# Gate_Drivers.net
KiCad netlist of a schematic drawn in Altium Designer
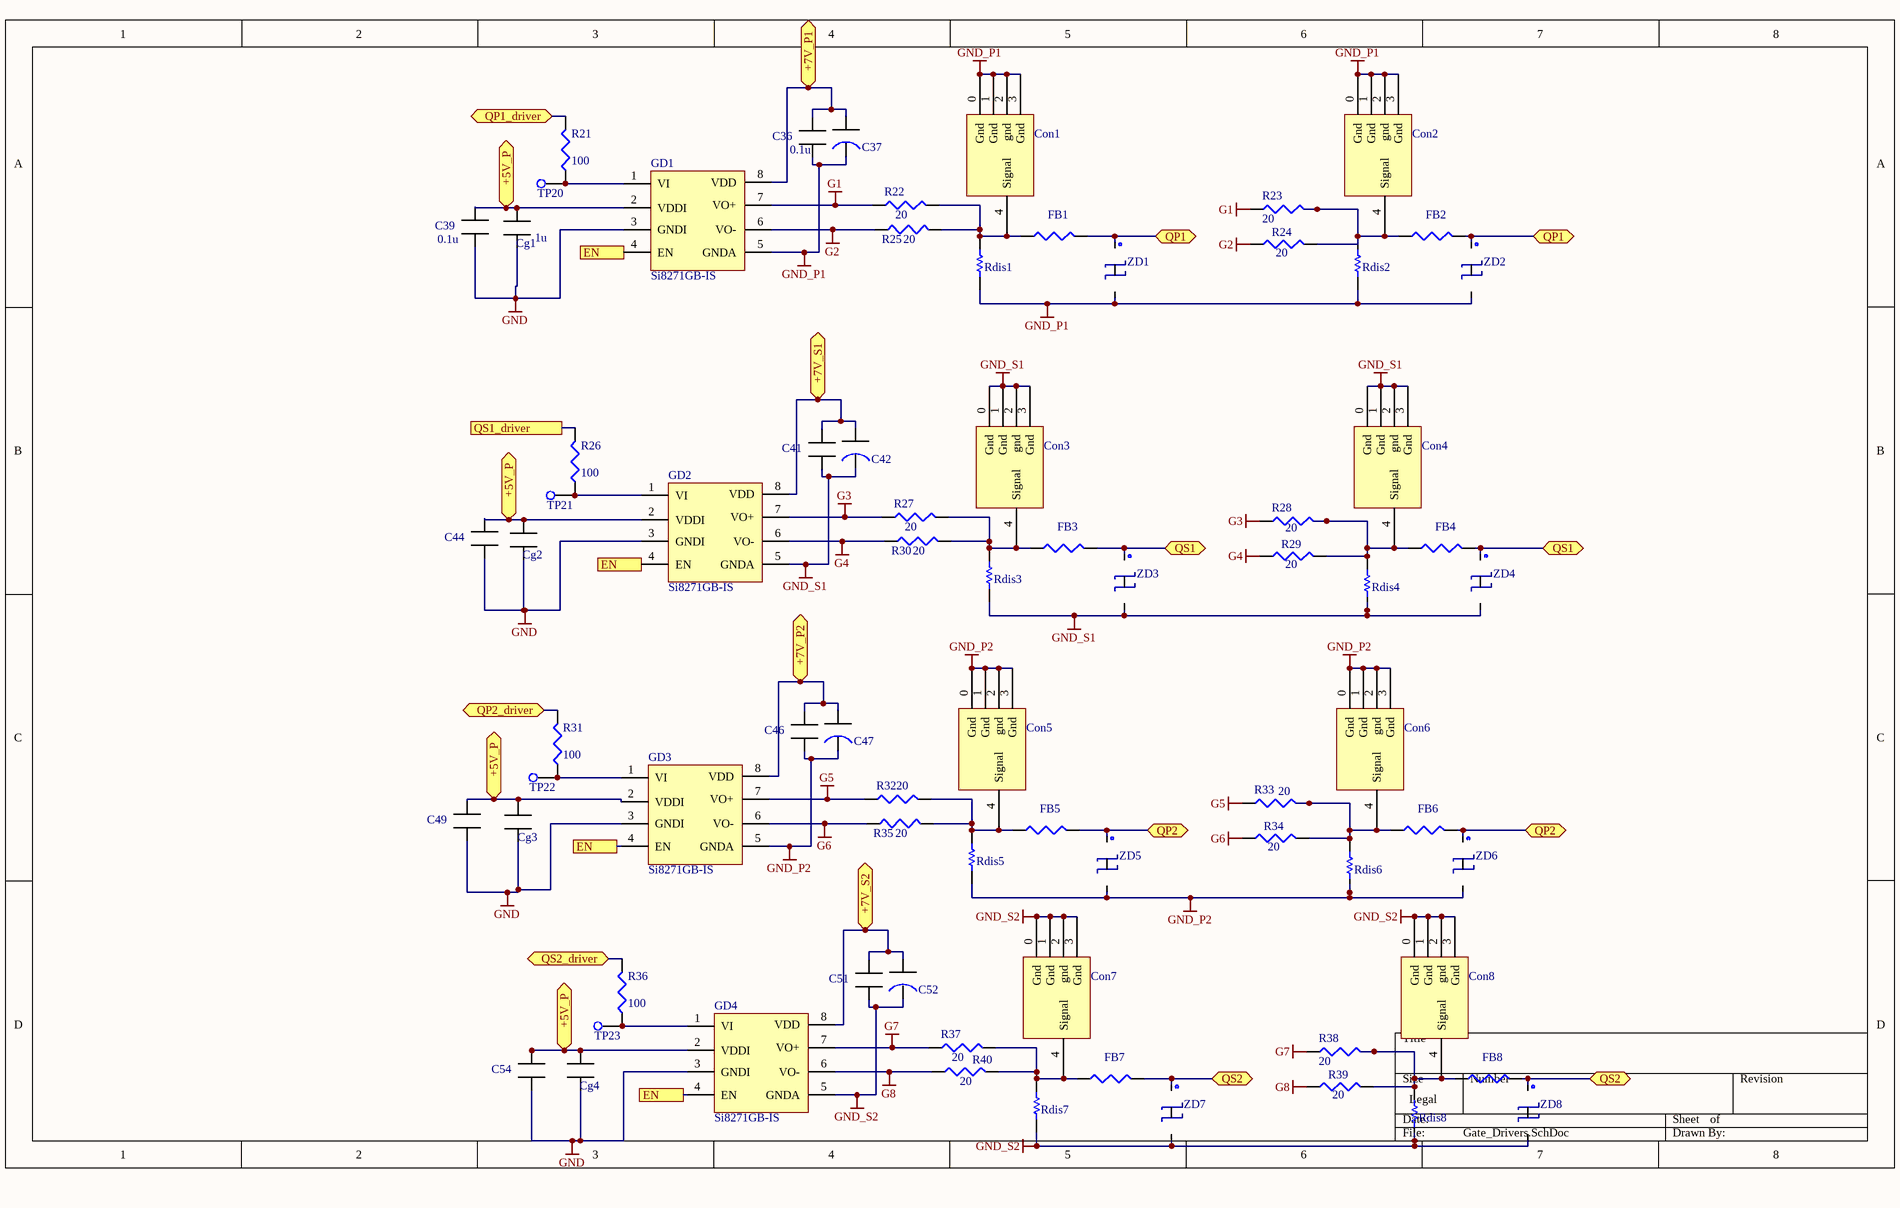
[diagram p0: Gate_Drivers.SchDoc]

(export (version "E")
  (design (tool "Eeschema 10.0.6"))
  (components
    (comp (ref "C36")
      (value "100nF")
      (footprint "Cap_SMD")
      (fields (field (name "ALTIUM_UNNAMED_1") "0.1u"))
      (libsource (lib "Schlib1") (part "Cap_SMD"))
    )
    (comp (ref "C37")
      (value "22uF")
      (footprint "Cap_tantalum")
      (libsource (lib "Schlib1") (part "Cap_tantalum"))
    )
    (comp (ref "C39")
      (value "100nF")
      (footprint "Cap_SMD")
      (fields (field (name "ALTIUM_UNNAMED_1") "0.1u"))
      (libsource (lib "Schlib1") (part "Cap_SMD"))
    )
    (comp (ref "C41") (value "100nF") (footprint "Cap_SMD") (libsource (lib "Schlib1") (part "Cap_SMD")))
    (comp (ref "C42")
      (value "22uF")
      (footprint "Cap_tantalum")
      (libsource (lib "Schlib1") (part "Cap_tantalum"))
    )
    (comp (ref "C44") (value "100nF") (footprint "Cap_SMD") (libsource (lib "Schlib1") (part "Cap_SMD")))
    (comp (ref "C46") (value "100nF") (footprint "Cap_SMD") (libsource (lib "Schlib1") (part "Cap_SMD")))
    (comp (ref "C47")
      (value "22uF")
      (footprint "Cap_tantalum")
      (libsource (lib "Schlib1") (part "Cap_tantalum"))
    )
    (comp (ref "C49") (value "100nF") (footprint "Cap_SMD") (libsource (lib "Schlib1") (part "Cap_SMD")))
    (comp (ref "C51") (value "100nF") (footprint "Cap_SMD") (libsource (lib "Schlib1") (part "Cap_SMD")))
    (comp (ref "C52")
      (value "22uF")
      (footprint "Cap_tantalum")
      (libsource (lib "Schlib1") (part "Cap_tantalum"))
    )
    (comp (ref "C54") (value "100nF") (footprint "Cap_SMD") (libsource (lib "Schlib1") (part "Cap_SMD")))
    (comp (ref "Cg1")
      (value "100nF")
      (footprint "Cap_SMD")
      (fields (field (name "ALTIUM_UNNAMED_1") "1u"))
      (libsource (lib "Schlib1") (part "Cap_SMD"))
    )
    (comp (ref "Cg2") (value "100nF") (footprint "Cap_SMD") (libsource (lib "Schlib1") (part "Cap_SMD")))
    (comp (ref "Cg3") (value "100nF") (footprint "Cap_SMD") (libsource (lib "Schlib1") (part "Cap_SMD")))
    (comp (ref "Cg4") (value "100nF") (footprint "Cap_SMD") (libsource (lib "Schlib1") (part "Cap_SMD")))
    (comp (ref "Con1")
      (value "Component_1")
      (footprint "PCBComponent_1")
      (libsource (lib "pcb_connector") (part "Component_1"))
    )
    (comp (ref "Con2")
      (value "Component_1")
      (footprint "PCBComponent_1")
      (libsource (lib "pcb_connector") (part "Component_1"))
    )
    (comp (ref "Con3")
      (value "Component_1")
      (footprint "PCBComponent_1")
      (libsource (lib "pcb_connector") (part "Component_1"))
    )
    (comp (ref "Con4")
      (value "Component_1")
      (footprint "PCBComponent_1")
      (libsource (lib "pcb_connector") (part "Component_1"))
    )
    (comp (ref "Con5")
      (value "Component_1")
      (footprint "PCBComponent_1")
      (libsource (lib "pcb_connector") (part "Component_1"))
    )
    (comp (ref "Con6")
      (value "Component_1")
      (footprint "PCBComponent_1")
      (libsource (lib "pcb_connector") (part "Component_1"))
    )
    (comp (ref "Con7")
      (value "Component_1")
      (footprint "PCBComponent_1")
      (libsource (lib "pcb_connector") (part "Component_1"))
    )
    (comp (ref "Con8")
      (value "Component_1")
      (footprint "PCBComponent_1")
      (libsource (lib "pcb_connector") (part "Component_1"))
    )
    (comp (ref "FB1")
      (value "Res3")
      (footprint "J1-0603")
      (description "Resistor")
      (fields (field (name "PUBLISHER") "Altium Limited"))
      (libsource (lib "Miscellaneous Devices") (part "Res3"))
    )
    (comp (ref "FB2")
      (value "Res3")
      (footprint "J1-0603")
      (description "Resistor")
      (fields (field (name "PUBLISHER") "Altium Limited"))
      (libsource (lib "Miscellaneous Devices") (part "Res3"))
    )
    (comp (ref "FB3")
      (value "Res3")
      (footprint "J1-0603")
      (description "Resistor")
      (fields (field (name "PUBLISHER") "Altium Limited"))
      (libsource (lib "Miscellaneous Devices") (part "Res3"))
    )
    (comp (ref "FB4")
      (value "Res3")
      (footprint "J1-0603")
      (description "Resistor")
      (fields (field (name "PUBLISHER") "Altium Limited"))
      (libsource (lib "Miscellaneous Devices") (part "Res3"))
    )
    (comp (ref "FB5")
      (value "Res3")
      (footprint "J1-0603")
      (description "Resistor")
      (fields (field (name "PUBLISHER") "Altium Limited"))
      (libsource (lib "Miscellaneous Devices") (part "Res3"))
    )
    (comp (ref "FB6")
      (value "Res3")
      (footprint "J1-0603")
      (description "Resistor")
      (fields (field (name "PUBLISHER") "Altium Limited"))
      (libsource (lib "Miscellaneous Devices") (part "Res3"))
    )
    (comp (ref "FB7")
      (value "Res3")
      (footprint "J1-0603")
      (description "Resistor")
      (fields (field (name "PUBLISHER") "Altium Limited"))
      (libsource (lib "Miscellaneous Devices") (part "Res3"))
    )
    (comp (ref "FB8")
      (value "Res3")
      (footprint "J1-0603")
      (description "Resistor")
      (fields (field (name "PUBLISHER") "Altium Limited"))
      (libsource (lib "Miscellaneous Devices") (part "Res3"))
    )
    (comp (ref "GD1")
      (value "Si8271GB-IS")
      (footprint "Si8271")
      (libsource (lib "Gan_cuk converter") (part "Si8271GB-IS"))
    )
    (comp (ref "GD2")
      (value "Si8271GB-IS")
      (footprint "Si8271")
      (libsource (lib "Gan_cuk converter") (part "Si8271GB-IS"))
    )
    (comp (ref "GD3")
      (value "Si8271GB-IS")
      (footprint "Si8271")
      (libsource (lib "Gan_cuk converter") (part "Si8271GB-IS"))
    )
    (comp (ref "GD4")
      (value "Si8271GB-IS")
      (footprint "Si8271")
      (libsource (lib "Gan_cuk converter") (part "Si8271GB-IS"))
    )
    (comp (ref "R21")
      (value "100")
      (footprint "J1-0603")
      (description "Resistor")
      (fields (field (name "Comment") "Res3") (field (name "PUBLISHER") "Altium Limited"))
      (libsource (lib "Miscellaneous Devices") (part "Res3"))
    )
    (comp (ref "R22")
      (value "20")
      (footprint "J1-0603")
      (description "Resistor")
      (fields (field (name "Comment") "Res3") (field (name "PUBLISHER") "Altium Limited"))
      (libsource (lib "Miscellaneous Devices") (part "Res3"))
    )
    (comp (ref "R23")
      (value "20")
      (footprint "J1-0603")
      (description "Resistor")
      (fields (field (name "Comment") "Res3") (field (name "PUBLISHER") "Altium Limited"))
      (libsource (lib "Miscellaneous Devices") (part "Res3"))
    )
    (comp (ref "R24")
      (value "20")
      (footprint "J1-0603")
      (description "Resistor")
      (fields (field (name "PUBLISHER") "Altium Limited"))
      (libsource (lib "Miscellaneous Devices") (part "Res3"))
    )
    (comp (ref "R25")
      (value "20")
      (footprint "J1-0603")
      (description "Resistor")
      (fields (field (name "Comment") "Res3") (field (name "PUBLISHER") "Altium Limited"))
      (libsource (lib "Miscellaneous Devices") (part "Res3"))
    )
    (comp (ref "R26")
      (value "100")
      (footprint "J1-0603")
      (description "Resistor")
      (fields (field (name "Comment") "Res3") (field (name "PUBLISHER") "Altium Limited"))
      (libsource (lib "Miscellaneous Devices") (part "Res3"))
    )
    (comp (ref "R27")
      (value "20")
      (footprint "J1-0603")
      (description "Resistor")
      (fields (field (name "Comment") "Res3") (field (name "PUBLISHER") "Altium Limited"))
      (libsource (lib "Miscellaneous Devices") (part "Res3"))
    )
    (comp (ref "R28")
      (value "20")
      (footprint "J1-0603")
      (description "Resistor")
      (fields (field (name "Comment") "Res3") (field (name "PUBLISHER") "Altium Limited"))
      (libsource (lib "Miscellaneous Devices") (part "Res3"))
    )
    (comp (ref "R29")
      (value "20")
      (footprint "J1-0603")
      (description "Resistor")
      (fields (field (name "PUBLISHER") "Altium Limited"))
      (libsource (lib "Miscellaneous Devices") (part "Res3"))
    )
    (comp (ref "R30")
      (value "20")
      (footprint "J1-0603")
      (description "Resistor")
      (fields (field (name "Comment") "Res3") (field (name "PUBLISHER") "Altium Limited"))
      (libsource (lib "Miscellaneous Devices") (part "Res3"))
    )
    (comp (ref "R31")
      (value "100")
      (footprint "J1-0603")
      (description "Resistor")
      (fields (field (name "Comment") "Res3") (field (name "PUBLISHER") "Altium Limited"))
      (libsource (lib "Miscellaneous Devices") (part "Res3"))
    )
    (comp (ref "R32")
      (value "20")
      (footprint "J1-0603")
      (description "Resistor")
      (fields (field (name "Comment") "Res3") (field (name "PUBLISHER") "Altium Limited"))
      (libsource (lib "Miscellaneous Devices") (part "Res3"))
    )
    (comp (ref "R33")
      (value "20")
      (footprint "J1-0603")
      (description "Resistor")
      (fields (field (name "Comment") "Res3") (field (name "PUBLISHER") "Altium Limited"))
      (libsource (lib "Miscellaneous Devices") (part "Res3"))
    )
    (comp (ref "R34")
      (value "20")
      (footprint "J1-0603")
      (description "Resistor")
      (fields (field (name "PUBLISHER") "Altium Limited"))
      (libsource (lib "Miscellaneous Devices") (part "Res3"))
    )
    (comp (ref "R35")
      (value "20")
      (footprint "J1-0603")
      (description "Resistor")
      (fields (field (name "Comment") "Res3") (field (name "PUBLISHER") "Altium Limited"))
      (libsource (lib "Miscellaneous Devices") (part "Res3"))
    )
    (comp (ref "R36")
      (value "100")
      (footprint "J1-0603")
      (description "Resistor")
      (fields (field (name "Comment") "Res3") (field (name "PUBLISHER") "Altium Limited"))
      (libsource (lib "Miscellaneous Devices") (part "Res3"))
    )
    (comp (ref "R37")
      (value "20")
      (footprint "J1-0603")
      (description "Resistor")
      (fields (field (name "Comment") "Res3") (field (name "PUBLISHER") "Altium Limited"))
      (libsource (lib "Miscellaneous Devices") (part "Res3"))
    )
    (comp (ref "R38")
      (value "20")
      (footprint "J1-0603")
      (description "Resistor")
      (fields (field (name "Comment") "Res3") (field (name "PUBLISHER") "Altium Limited"))
      (libsource (lib "Miscellaneous Devices") (part "Res3"))
    )
    (comp (ref "R39")
      (value "20")
      (footprint "J1-0603")
      (description "Resistor")
      (fields (field (name "PUBLISHER") "Altium Limited"))
      (libsource (lib "Miscellaneous Devices") (part "Res3"))
    )
    (comp (ref "R40")
      (value "20")
      (footprint "J1-0603")
      (description "Resistor")
      (fields (field (name "Comment") "Res3") (field (name "PUBLISHER") "Altium Limited"))
      (libsource (lib "Miscellaneous Devices") (part "Res3"))
    )
    (comp (ref "Rdis1")
      (value "res_smd")
      (footprint "J1-0603")
      (description "smd_res")
      (libsource (lib "Schlib1") (part "res_smd"))
    )
    (comp (ref "Rdis2")
      (value "res_smd")
      (footprint "J1-0603")
      (description "smd_res")
      (libsource (lib "Schlib1") (part "res_smd"))
    )
    (comp (ref "Rdis3")
      (value "res_smd")
      (footprint "J1-0603")
      (description "smd_res")
      (libsource (lib "Schlib1") (part "res_smd"))
    )
    (comp (ref "Rdis4")
      (value "res_smd")
      (footprint "J1-0603")
      (description "smd_res")
      (libsource (lib "Schlib1") (part "res_smd"))
    )
    (comp (ref "Rdis5")
      (value "res_smd")
      (footprint "J1-0603")
      (description "smd_res")
      (libsource (lib "Schlib1") (part "res_smd"))
    )
    (comp (ref "Rdis6")
      (value "res_smd")
      (footprint "J1-0603")
      (description "smd_res")
      (libsource (lib "Schlib1") (part "res_smd"))
    )
    (comp (ref "Rdis7")
      (value "res_smd")
      (footprint "J1-0603")
      (description "smd_res")
      (libsource (lib "Schlib1") (part "res_smd"))
    )
    (comp (ref "Rdis8")
      (value "res_smd")
      (footprint "J1-0603")
      (description "smd_res")
      (libsource (lib "Schlib1") (part "res_smd"))
    )
    (comp (ref "TP20")
      (value "Test Point")
      (footprint "Test Point")
      (libsource (lib "Gan_cuk converter") (part "Test Point"))
    )
    (comp (ref "TP21")
      (value "Test Point")
      (footprint "Test Point")
      (libsource (lib "Gan_cuk converter") (part "Test Point"))
    )
    (comp (ref "TP22")
      (value "Test Point")
      (footprint "Test Point")
      (libsource (lib "Gan_cuk converter") (part "Test Point"))
    )
    (comp (ref "TP23")
      (value "Test Point")
      (footprint "Test Point")
      (libsource (lib "Gan_cuk converter") (part "Test Point"))
    )
    (comp (ref "ZD1")
      (value "8.2 v")
      (footprint "Zener Diode")
      (description "DZ23C8V2-7-F")
      (libsource (lib "Gan_cuk converter") (part "Zener_diode"))
    )
    (comp (ref "ZD2")
      (value "8.2 v")
      (footprint "Zener Diode")
      (description "DZ23C8V2-7-F")
      (libsource (lib "Gan_cuk converter") (part "Zener_diode"))
    )
    (comp (ref "ZD3")
      (value "8.2 v")
      (footprint "Zener Diode")
      (description "DZ23C8V2-7-F")
      (libsource (lib "Gan_cuk converter") (part "Zener_diode"))
    )
    (comp (ref "ZD4")
      (value "8.2 v")
      (footprint "Zener Diode")
      (description "DZ23C8V2-7-F")
      (libsource (lib "Gan_cuk converter") (part "Zener_diode"))
    )
    (comp (ref "ZD5")
      (value "8.2 v")
      (footprint "Zener Diode")
      (description "DZ23C8V2-7-F")
      (libsource (lib "Gan_cuk converter") (part "Zener_diode"))
    )
    (comp (ref "ZD6")
      (value "8.2 v")
      (footprint "Zener Diode")
      (description "DZ23C8V2-7-F")
      (libsource (lib "Gan_cuk converter") (part "Zener_diode"))
    )
    (comp (ref "ZD7")
      (value "8.2 v")
      (footprint "Zener Diode")
      (description "DZ23C8V2-7-F")
      (libsource (lib "Gan_cuk converter") (part "Zener_diode"))
    )
    (comp (ref "ZD8")
      (value "8.2 v")
      (footprint "Zener Diode")
      (description "DZ23C8V2-7-F")
      (libsource (lib "Gan_cuk converter") (part "Zener_diode"))
    )
  )
  (nets
    (net (code "1") (name "/+5V_P") (class "Default")
      (node (ref "C39") (pin "1") (pintype "passive"))
      (node (ref "C44") (pin "1") (pintype "passive"))
      (node (ref "C49") (pin "1") (pintype "passive"))
      (node (ref "C54") (pin "1") (pintype "passive"))
      (node (ref "Cg1") (pin "1") (pintype "passive"))
      (node (ref "Cg2") (pin "1") (pintype "passive"))
      (node (ref "Cg3") (pin "1") (pintype "passive"))
      (node (ref "Cg4") (pin "1") (pintype "passive"))
      (node (ref "GD1") (pin "2") (pinfunction "VDDI_2") (pintype "passive"))
      (node (ref "GD2") (pin "2") (pinfunction "VDDI_2") (pintype "passive"))
      (node (ref "GD3") (pin "2") (pinfunction "VDDI_2") (pintype "passive"))
      (node (ref "GD4") (pin "2") (pinfunction "VDDI_2") (pintype "passive"))
    )
    (net (code "2") (name "/+7V_P1") (class "Default")
      (node (ref "C36") (pin "1") (pintype "passive"))
      (node (ref "C37") (pin "1") (pintype "passive"))
      (node (ref "GD1") (pin "8") (pinfunction "VDD_8") (pintype "passive"))
    )
    (net (code "3") (name "/+7V_P2") (class "Default")
      (node (ref "C46") (pin "1") (pintype "passive"))
      (node (ref "C47") (pin "1") (pintype "passive"))
      (node (ref "GD3") (pin "8") (pinfunction "VDD_8") (pintype "passive"))
    )
    (net (code "4") (name "/+7V_S1") (class "Default")
      (node (ref "C41") (pin "1") (pintype "passive"))
      (node (ref "C42") (pin "1") (pintype "passive"))
      (node (ref "GD2") (pin "8") (pinfunction "VDD_8") (pintype "passive"))
    )
    (net (code "5") (name "/+7V_S2") (class "Default")
      (node (ref "C51") (pin "1") (pintype "passive"))
      (node (ref "C52") (pin "1") (pintype "passive"))
      (node (ref "GD4") (pin "8") (pinfunction "VDD_8") (pintype "passive"))
    )
    (net (code "6") (name "/EN") (class "Default")
      (node (ref "GD1") (pin "4") (pinfunction "EN_4") (pintype "passive"))
      (node (ref "GD2") (pin "4") (pinfunction "EN_4") (pintype "passive"))
      (node (ref "GD3") (pin "4") (pinfunction "EN_4") (pintype "passive"))
      (node (ref "GD4") (pin "4") (pinfunction "EN_4") (pintype "passive"))
    )
    (net (code "7") (name "/QP1") (class "Default")
      (node (ref "FB1") (pin "2") (pinfunction "2_2") (pintype "passive"))
      (node (ref "FB2") (pin "2") (pinfunction "2_2") (pintype "passive"))
      (node (ref "ZD1") (pin "1") (pinfunction "1_1") (pintype "passive"))
      (node (ref "ZD2") (pin "1") (pinfunction "1_1") (pintype "passive"))
    )
    (net (code "8") (name "/QP1_driver") (class "Default")
      (node (ref "R21") (pin "2") (pinfunction "2_2") (pintype "passive"))
    )
    (net (code "9") (name "/QP2") (class "Default")
      (node (ref "FB5") (pin "2") (pinfunction "2_2") (pintype "passive"))
      (node (ref "FB6") (pin "2") (pinfunction "2_2") (pintype "passive"))
      (node (ref "ZD5") (pin "1") (pinfunction "1_1") (pintype "passive"))
      (node (ref "ZD6") (pin "1") (pinfunction "1_1") (pintype "passive"))
    )
    (net (code "10") (name "/QP2_driver") (class "Default")
      (node (ref "R31") (pin "2") (pinfunction "2_2") (pintype "passive"))
    )
    (net (code "11") (name "/QS1") (class "Default")
      (node (ref "FB3") (pin "2") (pinfunction "2_2") (pintype "passive"))
      (node (ref "FB4") (pin "2") (pinfunction "2_2") (pintype "passive"))
      (node (ref "ZD3") (pin "1") (pinfunction "1_1") (pintype "passive"))
      (node (ref "ZD4") (pin "1") (pinfunction "1_1") (pintype "passive"))
    )
    (net (code "12") (name "/QS1_driver") (class "Default")
      (node (ref "R26") (pin "2") (pinfunction "2_2") (pintype "passive"))
    )
    (net (code "13") (name "/QS2") (class "Default")
      (node (ref "FB7") (pin "2") (pinfunction "2_2") (pintype "passive"))
      (node (ref "FB8") (pin "2") (pinfunction "2_2") (pintype "passive"))
      (node (ref "ZD7") (pin "1") (pinfunction "1_1") (pintype "passive"))
      (node (ref "ZD8") (pin "1") (pinfunction "1_1") (pintype "passive"))
    )
    (net (code "14") (name "/QS2_driver") (class "Default")
      (node (ref "R36") (pin "2") (pinfunction "2_2") (pintype "passive"))
    )
    (net (code "15") (name "G1") (class "Default")
      (node (ref "GD1") (pin "7") (pinfunction "VO+_7") (pintype "passive"))
      (node (ref "R22") (pin "1") (pinfunction "1_1") (pintype "passive"))
      (node (ref "R23") (pin "1") (pinfunction "1_1") (pintype "passive"))
    )
    (net (code "16") (name "G2") (class "Default")
      (node (ref "GD1") (pin "6") (pinfunction "VO-_6") (pintype "passive"))
      (node (ref "R24") (pin "1") (pinfunction "1_1") (pintype "passive"))
      (node (ref "R25") (pin "1") (pinfunction "1_1") (pintype "passive"))
    )
    (net (code "17") (name "G3") (class "Default")
      (node (ref "GD2") (pin "7") (pinfunction "VO+_7") (pintype "passive"))
      (node (ref "R27") (pin "1") (pinfunction "1_1") (pintype "passive"))
      (node (ref "R28") (pin "1") (pinfunction "1_1") (pintype "passive"))
    )
    (net (code "18") (name "G4") (class "Default")
      (node (ref "GD2") (pin "6") (pinfunction "VO-_6") (pintype "passive"))
      (node (ref "R29") (pin "1") (pinfunction "1_1") (pintype "passive"))
      (node (ref "R30") (pin "1") (pinfunction "1_1") (pintype "passive"))
    )
    (net (code "19") (name "G5") (class "Default")
      (node (ref "GD3") (pin "7") (pinfunction "VO+_7") (pintype "passive"))
      (node (ref "R32") (pin "1") (pinfunction "1_1") (pintype "passive"))
      (node (ref "R33") (pin "1") (pinfunction "1_1") (pintype "passive"))
    )
    (net (code "20") (name "G6") (class "Default")
      (node (ref "GD3") (pin "6") (pinfunction "VO-_6") (pintype "passive"))
      (node (ref "R34") (pin "1") (pinfunction "1_1") (pintype "passive"))
      (node (ref "R35") (pin "1") (pinfunction "1_1") (pintype "passive"))
    )
    (net (code "21") (name "G7") (class "Default")
      (node (ref "GD4") (pin "7") (pinfunction "VO+_7") (pintype "passive"))
      (node (ref "R37") (pin "1") (pinfunction "1_1") (pintype "passive"))
      (node (ref "R38") (pin "1") (pinfunction "1_1") (pintype "passive"))
    )
    (net (code "22") (name "G8") (class "Default")
      (node (ref "GD4") (pin "6") (pinfunction "VO-_6") (pintype "passive"))
      (node (ref "R39") (pin "1") (pinfunction "1_1") (pintype "passive"))
      (node (ref "R40") (pin "1") (pinfunction "1_1") (pintype "passive"))
    )
    (net (code "23") (name "GND") (class "Default")
      (node (ref "C39") (pin "2") (pintype "passive"))
      (node (ref "C44") (pin "2") (pintype "passive"))
      (node (ref "C49") (pin "2") (pintype "passive"))
      (node (ref "C54") (pin "2") (pintype "passive"))
      (node (ref "Cg1") (pin "2") (pintype "passive"))
      (node (ref "Cg2") (pin "2") (pintype "passive"))
      (node (ref "Cg3") (pin "2") (pintype "passive"))
      (node (ref "Cg4") (pin "2") (pintype "passive"))
      (node (ref "GD1") (pin "3") (pinfunction "GNDI_3") (pintype "passive"))
      (node (ref "GD2") (pin "3") (pinfunction "GNDI_3") (pintype "passive"))
      (node (ref "GD3") (pin "3") (pinfunction "GNDI_3") (pintype "passive"))
      (node (ref "GD4") (pin "3") (pinfunction "GNDI_3") (pintype "passive"))
    )
    (net (code "24") (name "GND_P1") (class "Default")
      (node (ref "C36") (pin "2") (pintype "passive"))
      (node (ref "C37") (pin "2") (pintype "passive"))
      (node (ref "Con1") (pin "0") (pinfunction "Gnd_0") (pintype "passive"))
      (node (ref "Con1") (pin "1") (pinfunction "Gnd_1") (pintype "passive"))
      (node (ref "Con1") (pin "2") (pinfunction "gnd_2") (pintype "passive"))
      (node (ref "Con1") (pin "3") (pinfunction "Gnd_3") (pintype "passive"))
      (node (ref "Con2") (pin "0") (pinfunction "Gnd_0") (pintype "passive"))
      (node (ref "Con2") (pin "1") (pinfunction "Gnd_1") (pintype "passive"))
      (node (ref "Con2") (pin "2") (pinfunction "gnd_2") (pintype "passive"))
      (node (ref "Con2") (pin "3") (pinfunction "Gnd_3") (pintype "passive"))
      (node (ref "GD1") (pin "5") (pinfunction "GNDA_5") (pintype "passive"))
      (node (ref "Rdis1") (pin "2") (pintype "passive"))
      (node (ref "Rdis2") (pin "2") (pintype "passive"))
      (node (ref "ZD1") (pin "2") (pinfunction "2_2") (pintype "passive"))
      (node (ref "ZD2") (pin "2") (pinfunction "2_2") (pintype "passive"))
    )
    (net (code "25") (name "GND_P2") (class "Default")
      (node (ref "C46") (pin "2") (pintype "passive"))
      (node (ref "C47") (pin "2") (pintype "passive"))
      (node (ref "Con5") (pin "0") (pinfunction "Gnd_0") (pintype "passive"))
      (node (ref "Con5") (pin "1") (pinfunction "Gnd_1") (pintype "passive"))
      (node (ref "Con5") (pin "2") (pinfunction "gnd_2") (pintype "passive"))
      (node (ref "Con5") (pin "3") (pinfunction "Gnd_3") (pintype "passive"))
      (node (ref "Con6") (pin "0") (pinfunction "Gnd_0") (pintype "passive"))
      (node (ref "Con6") (pin "1") (pinfunction "Gnd_1") (pintype "passive"))
      (node (ref "Con6") (pin "2") (pinfunction "gnd_2") (pintype "passive"))
      (node (ref "Con6") (pin "3") (pinfunction "Gnd_3") (pintype "passive"))
      (node (ref "GD3") (pin "5") (pinfunction "GNDA_5") (pintype "passive"))
      (node (ref "Rdis5") (pin "2") (pintype "passive"))
      (node (ref "Rdis6") (pin "2") (pintype "passive"))
      (node (ref "ZD5") (pin "2") (pinfunction "2_2") (pintype "passive"))
      (node (ref "ZD6") (pin "2") (pinfunction "2_2") (pintype "passive"))
    )
    (net (code "26") (name "GND_S1") (class "Default")
      (node (ref "C41") (pin "2") (pintype "passive"))
      (node (ref "C42") (pin "2") (pintype "passive"))
      (node (ref "Con3") (pin "0") (pinfunction "Gnd_0") (pintype "passive"))
      (node (ref "Con3") (pin "1") (pinfunction "Gnd_1") (pintype "passive"))
      (node (ref "Con3") (pin "2") (pinfunction "gnd_2") (pintype "passive"))
      (node (ref "Con3") (pin "3") (pinfunction "Gnd_3") (pintype "passive"))
      (node (ref "Con4") (pin "0") (pinfunction "Gnd_0") (pintype "passive"))
      (node (ref "Con4") (pin "1") (pinfunction "Gnd_1") (pintype "passive"))
      (node (ref "Con4") (pin "2") (pinfunction "gnd_2") (pintype "passive"))
      (node (ref "Con4") (pin "3") (pinfunction "Gnd_3") (pintype "passive"))
      (node (ref "GD2") (pin "5") (pinfunction "GNDA_5") (pintype "passive"))
      (node (ref "Rdis3") (pin "2") (pintype "passive"))
      (node (ref "Rdis4") (pin "2") (pintype "passive"))
      (node (ref "ZD3") (pin "2") (pinfunction "2_2") (pintype "passive"))
      (node (ref "ZD4") (pin "2") (pinfunction "2_2") (pintype "passive"))
    )
    (net (code "27") (name "GND_S2") (class "Default")
      (node (ref "C51") (pin "2") (pintype "passive"))
      (node (ref "C52") (pin "2") (pintype "passive"))
      (node (ref "Con7") (pin "0") (pinfunction "Gnd_0") (pintype "passive"))
      (node (ref "Con7") (pin "1") (pinfunction "Gnd_1") (pintype "passive"))
      (node (ref "Con7") (pin "2") (pinfunction "gnd_2") (pintype "passive"))
      (node (ref "Con7") (pin "3") (pinfunction "Gnd_3") (pintype "passive"))
      (node (ref "Con8") (pin "0") (pinfunction "Gnd_0") (pintype "passive"))
      (node (ref "Con8") (pin "1") (pinfunction "Gnd_1") (pintype "passive"))
      (node (ref "Con8") (pin "2") (pinfunction "gnd_2") (pintype "passive"))
      (node (ref "Con8") (pin "3") (pinfunction "Gnd_3") (pintype "passive"))
      (node (ref "GD4") (pin "5") (pinfunction "GNDA_5") (pintype "passive"))
      (node (ref "Rdis7") (pin "2") (pintype "passive"))
      (node (ref "Rdis8") (pin "2") (pintype "passive"))
      (node (ref "ZD7") (pin "2") (pinfunction "2_2") (pintype "passive"))
      (node (ref "ZD8") (pin "2") (pinfunction "2_2") (pintype "passive"))
    )
    (net (code "28") (name "Net-(Con1-Signal)") (class "Default")
      (node (ref "Con1") (pin "4") (pinfunction "Signal_4") (pintype "passive"))
      (node (ref "FB1") (pin "1") (pinfunction "1_1") (pintype "passive"))
      (node (ref "R22") (pin "2") (pinfunction "2_2") (pintype "passive"))
      (node (ref "R25") (pin "2") (pinfunction "2_2") (pintype "passive"))
      (node (ref "Rdis1") (pin "1") (pintype "passive"))
    )
    (net (code "29") (name "Net-(Con2-Signal)") (class "Default")
      (node (ref "Con2") (pin "4") (pinfunction "Signal_4") (pintype "passive"))
      (node (ref "FB2") (pin "1") (pinfunction "1_1") (pintype "passive"))
      (node (ref "R23") (pin "2") (pinfunction "2_2") (pintype "passive"))
      (node (ref "R24") (pin "2") (pinfunction "2_2") (pintype "passive"))
      (node (ref "Rdis2") (pin "1") (pintype "passive"))
    )
    (net (code "30") (name "Net-(Con3-Signal)") (class "Default")
      (node (ref "Con3") (pin "4") (pinfunction "Signal_4") (pintype "passive"))
      (node (ref "FB3") (pin "1") (pinfunction "1_1") (pintype "passive"))
      (node (ref "R27") (pin "2") (pinfunction "2_2") (pintype "passive"))
      (node (ref "R30") (pin "2") (pinfunction "2_2") (pintype "passive"))
      (node (ref "Rdis3") (pin "1") (pintype "passive"))
    )
    (net (code "31") (name "Net-(Con4-Signal)") (class "Default")
      (node (ref "Con4") (pin "4") (pinfunction "Signal_4") (pintype "passive"))
      (node (ref "FB4") (pin "1") (pinfunction "1_1") (pintype "passive"))
      (node (ref "R28") (pin "2") (pinfunction "2_2") (pintype "passive"))
      (node (ref "R29") (pin "2") (pinfunction "2_2") (pintype "passive"))
      (node (ref "Rdis4") (pin "1") (pintype "passive"))
    )
    (net (code "32") (name "Net-(Con5-Signal)") (class "Default")
      (node (ref "Con5") (pin "4") (pinfunction "Signal_4") (pintype "passive"))
      (node (ref "FB5") (pin "1") (pinfunction "1_1") (pintype "passive"))
      (node (ref "R32") (pin "2") (pinfunction "2_2") (pintype "passive"))
      (node (ref "R35") (pin "2") (pinfunction "2_2") (pintype "passive"))
      (node (ref "Rdis5") (pin "1") (pintype "passive"))
    )
    (net (code "33") (name "Net-(Con6-Signal)") (class "Default")
      (node (ref "Con6") (pin "4") (pinfunction "Signal_4") (pintype "passive"))
      (node (ref "FB6") (pin "1") (pinfunction "1_1") (pintype "passive"))
      (node (ref "R33") (pin "2") (pinfunction "2_2") (pintype "passive"))
      (node (ref "R34") (pin "2") (pinfunction "2_2") (pintype "passive"))
      (node (ref "Rdis6") (pin "1") (pintype "passive"))
    )
    (net (code "34") (name "Net-(Con7-Signal)") (class "Default")
      (node (ref "Con7") (pin "4") (pinfunction "Signal_4") (pintype "passive"))
      (node (ref "FB7") (pin "1") (pinfunction "1_1") (pintype "passive"))
      (node (ref "R37") (pin "2") (pinfunction "2_2") (pintype "passive"))
      (node (ref "R40") (pin "2") (pinfunction "2_2") (pintype "passive"))
      (node (ref "Rdis7") (pin "1") (pintype "passive"))
    )
    (net (code "35") (name "Net-(Con8-Signal)") (class "Default")
      (node (ref "Con8") (pin "4") (pinfunction "Signal_4") (pintype "passive"))
      (node (ref "FB8") (pin "1") (pinfunction "1_1") (pintype "passive"))
      (node (ref "R38") (pin "2") (pinfunction "2_2") (pintype "passive"))
      (node (ref "R39") (pin "2") (pinfunction "2_2") (pintype "passive"))
      (node (ref "Rdis8") (pin "1") (pintype "passive"))
    )
    (net (code "36") (name "Net-(GD1-VI)") (class "Default")
      (node (ref "GD1") (pin "1") (pinfunction "VI_1") (pintype "passive"))
      (node (ref "R21") (pin "1") (pinfunction "1_1") (pintype "passive"))
      (node (ref "TP20") (pin "1") (pinfunction "TP?_1") (pintype "passive"))
    )
    (net (code "37") (name "Net-(GD2-VI)") (class "Default")
      (node (ref "GD2") (pin "1") (pinfunction "VI_1") (pintype "passive"))
      (node (ref "R26") (pin "1") (pinfunction "1_1") (pintype "passive"))
      (node (ref "TP21") (pin "1") (pinfunction "TP?_1") (pintype "passive"))
    )
    (net (code "38") (name "Net-(GD3-VI)") (class "Default")
      (node (ref "GD3") (pin "1") (pinfunction "VI_1") (pintype "passive"))
      (node (ref "R31") (pin "1") (pinfunction "1_1") (pintype "passive"))
      (node (ref "TP22") (pin "1") (pinfunction "TP?_1") (pintype "passive"))
    )
    (net (code "39") (name "Net-(GD4-VI)") (class "Default")
      (node (ref "GD4") (pin "1") (pinfunction "VI_1") (pintype "passive"))
      (node (ref "R36") (pin "1") (pinfunction "1_1") (pintype "passive"))
      (node (ref "TP23") (pin "1") (pinfunction "TP?_1") (pintype "passive"))
    )
    (net (code "40") (name "unconnected-(ZD1-Pad3)") (class "Default")
      (node (ref "ZD1") (pin "3") (pinfunction "3_3") (pintype "passive"))
    )
    (net (code "41") (name "unconnected-(ZD2-Pad3)") (class "Default")
      (node (ref "ZD2") (pin "3") (pinfunction "3_3") (pintype "passive"))
    )
    (net (code "42") (name "unconnected-(ZD3-Pad3)") (class "Default")
      (node (ref "ZD3") (pin "3") (pinfunction "3_3") (pintype "passive"))
    )
    (net (code "43") (name "unconnected-(ZD4-Pad3)") (class "Default")
      (node (ref "ZD4") (pin "3") (pinfunction "3_3") (pintype "passive"))
    )
    (net (code "44") (name "unconnected-(ZD5-Pad3)") (class "Default")
      (node (ref "ZD5") (pin "3") (pinfunction "3_3") (pintype "passive"))
    )
    (net (code "45") (name "unconnected-(ZD6-Pad3)") (class "Default")
      (node (ref "ZD6") (pin "3") (pinfunction "3_3") (pintype "passive"))
    )
    (net (code "46") (name "unconnected-(ZD7-Pad3)") (class "Default")
      (node (ref "ZD7") (pin "3") (pinfunction "3_3") (pintype "passive"))
    )
    (net (code "47") (name "unconnected-(ZD8-Pad3)") (class "Default")
      (node (ref "ZD8") (pin "3") (pinfunction "3_3") (pintype "passive"))
    )
  )
)
